# STM32F7.net
KiCad netlist of a schematic drawn in Altium Designer
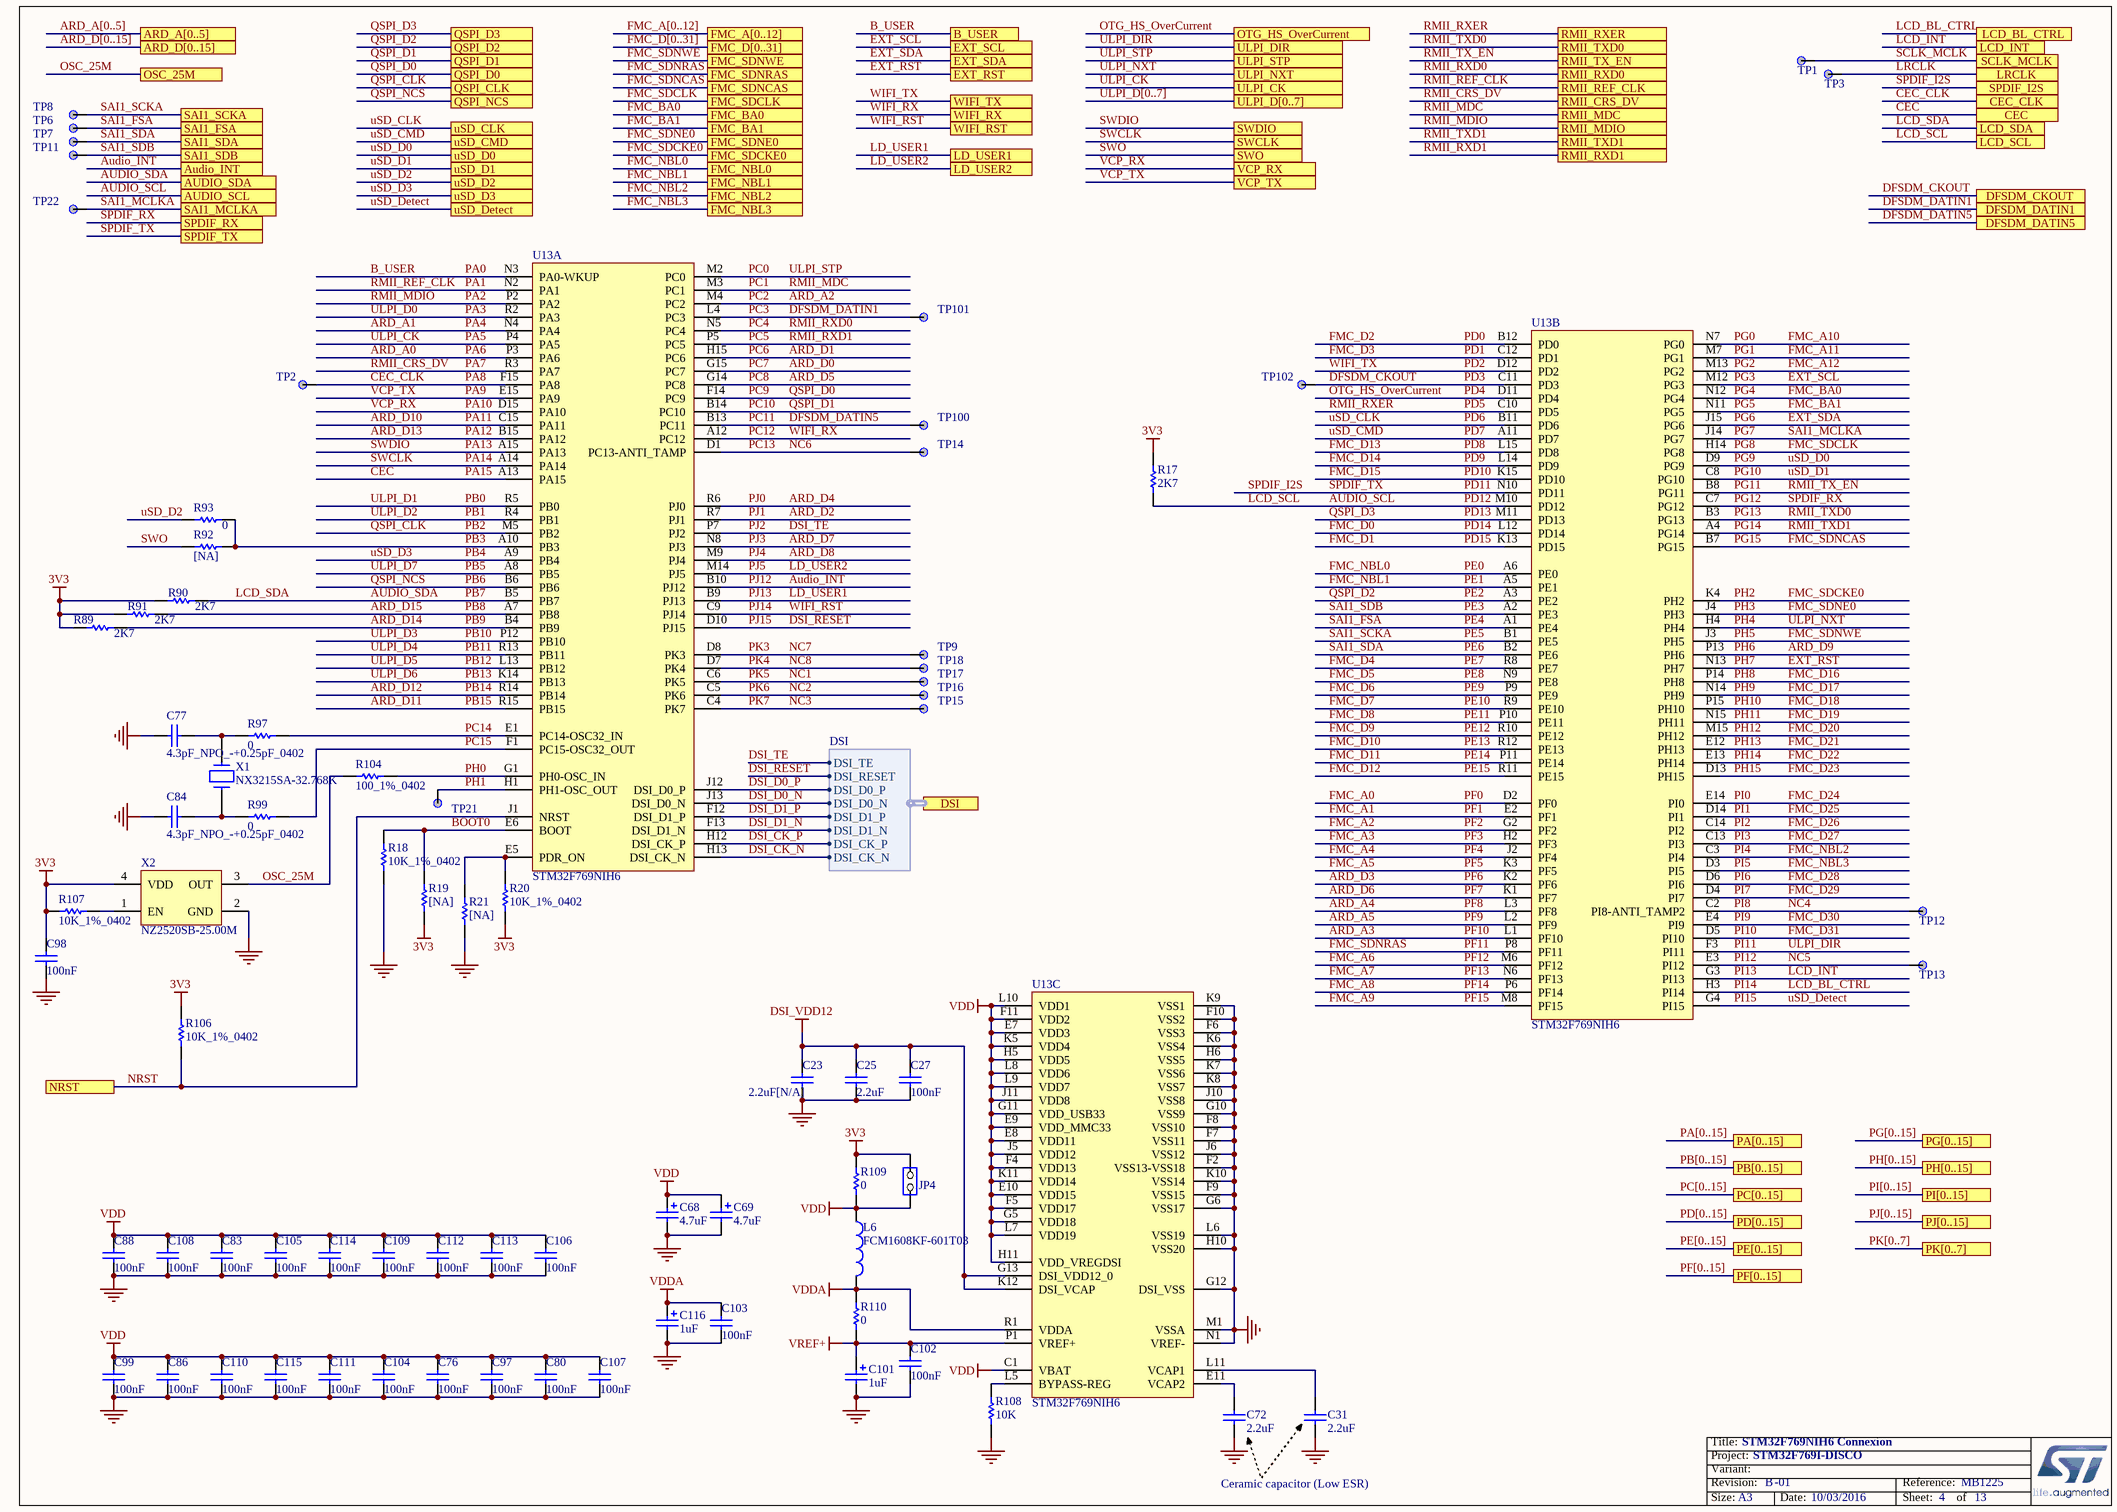
[diagram p0: STM32F7.SchDoc]

(export (version "E")
  (design (tool "Eeschema 10.0.6"))
  (components
    (comp (ref "C23")
      (value "2.2uF[N/A]")
      (footprint "1206C")
      (description "Capacitor,2.2uF,16V, X7R,10%,1206,YAGEO")
      (libsource (lib "MCD_TOOLS_CAPACITOR") (part "Cap_2.2uF_X7R_10%_1206"))
    )
    (comp (ref "C25")
      (value "2.2uF")
      (footprint "0603C")
      (description "Capacitor,2.2uF,10V, X5R,10%,0603,YAGEO")
      (libsource (lib "MCD_TOOLS_CAPACITOR") (part "Cap_2.2uF_X5R_10%_0603"))
    )
    (comp (ref "C27")
      (value "100nF")
      (footprint "0402C")
      (description "Capacitor,100nF,16V,X7R,10%,0402,YAGEO")
      (libsource (lib "MCD_TOOLS_CAPACITOR") (part "Cap_100nF_X7R_10%_0402"))
    )
    (comp (ref "C31")
      (value "2.2uF")
      (footprint "1206C")
      (description "Capacitor,2.2uF,16V, X7R,10%,1206,YAGEO")
      (libsource (lib "MCD_TOOLS") (part "Cap_2.2uF_X7R_10%_1206"))
    )
    (comp (ref "C68")
      (value "4.7uF")
      (footprint "TAN-A")
      (description "Polarized Capacitor,4.7uF,16V,10%,typeA,AVX")
      (libsource (lib "MCD_TOOLS") (part "Cap_4.7uF_POL_10%_TANA"))
    )
    (comp (ref "C69")
      (value "4.7uF")
      (footprint "TAN-A")
      (description "Polarized Capacitor,4.7uF,16V,10%,typeA,AVX")
      (libsource (lib "MCD_TOOLS") (part "Cap_4.7uF_POL_10%_TANA"))
    )
    (comp (ref "C72")
      (value "2.2uF")
      (footprint "1206C")
      (description "Capacitor,2.2uF,16V, X7R,10%,1206,YAGEO")
      (libsource (lib "MCD_TOOLS") (part "Cap_2.2uF_X7R_10%_1206"))
    )
    (comp (ref "C76")
      (value "100nF")
      (footprint "0402C")
      (description "Capacitor,100nF,16V,X7R,10%,0402,YAGEO")
      (libsource (lib "MCD_TOOLS") (part "Cap_100nF_X7R_10%_0402"))
    )
    (comp (ref "C77")
      (value "4.3pF_NPO_-+0.25pF_0402")
      (footprint "0402C")
      (description "Capacitor, 4.3pF, 16V, NPO, -+0.25pF, 0402, KEMET")
      (libsource (lib "MCD_TOOLS_CAPACITOR") (part "Cap_4.3pF_NPO_-+0.25pF_0402"))
    )
    (comp (ref "C80")
      (value "100nF")
      (footprint "0402C")
      (description "Capacitor,100nF,16V,X7R,10%,0402,YAGEO")
      (libsource (lib "MCD_TOOLS") (part "Cap_100nF_X7R_10%_0402"))
    )
    (comp (ref "C83")
      (value "100nF")
      (footprint "0402C")
      (description "Capacitor,100nF,16V,X7R,10%,0402,YAGEO")
      (libsource (lib "MCD_TOOLS") (part "Cap_100nF_X7R_10%_0402"))
    )
    (comp (ref "C84")
      (value "4.3pF_NPO_-+0.25pF_0402")
      (footprint "0402C")
      (description "Capacitor, 4.3pF, 16V, NPO, -+0.25pF, 0402, KEMET")
      (libsource (lib "MCD_TOOLS_CAPACITOR") (part "Cap_4.3pF_NPO_-+0.25pF_0402"))
    )
    (comp (ref "C86")
      (value "100nF")
      (footprint "0402C")
      (description "Capacitor,100nF,16V,X7R,10%,0402,YAGEO")
      (libsource (lib "MCD_TOOLS") (part "Cap_100nF_X7R_10%_0402"))
    )
    (comp (ref "C88")
      (value "100nF")
      (footprint "0402C")
      (description "Capacitor,100nF,16V,X7R,10%,0402,YAGEO")
      (libsource (lib "MCD_TOOLS") (part "Cap_100nF_X7R_10%_0402"))
    )
    (comp (ref "C97")
      (value "100nF")
      (footprint "0402C")
      (description "Capacitor,100nF,16V,X7R,10%,0402,YAGEO")
      (libsource (lib "MCD_TOOLS") (part "Cap_100nF_X7R_10%_0402"))
    )
    (comp (ref "C98")
      (value "100nF")
      (footprint "0402C")
      (description "Capacitor,100nF,16V,X7R,10%,0402,YAGEO")
      (libsource (lib "MCD_TOOLS") (part "Cap_100nF_X7R_10%_0402"))
    )
    (comp (ref "C99")
      (value "100nF")
      (footprint "0402C")
      (description "Capacitor,100nF,16V,X7R,10%,0402,YAGEO")
      (libsource (lib "MCD_TOOLS") (part "Cap_100nF_X7R_10%_0402"))
    )
    (comp (ref "C101")
      (value "1uF")
      (footprint "TAN-A")
      (description "Polarized Capacitor,1uF,16V,10%,typeA,AVX")
      (libsource (lib "MCD_TOOLS") (part "Cap_1uF_POL_10%_TANA"))
    )
    (comp (ref "C102")
      (value "100nF")
      (footprint "0402C")
      (description "Capacitor,100nF,16V,X7R,10%,0402,YAGEO")
      (libsource (lib "MCD_TOOLS") (part "Cap_100nF_X7R_10%_0402"))
    )
    (comp (ref "C103")
      (value "100nF")
      (footprint "0402C")
      (description "Capacitor,100nF,16V,X7R,10%,0402,YAGEO")
      (libsource (lib "MCD_TOOLS") (part "Cap_100nF_X7R_10%_0402"))
    )
    (comp (ref "C104")
      (value "100nF")
      (footprint "0402C")
      (description "Capacitor,100nF,16V,X7R,10%,0402,YAGEO")
      (libsource (lib "MCD_TOOLS") (part "Cap_100nF_X7R_10%_0402"))
    )
    (comp (ref "C105")
      (value "100nF")
      (footprint "0402C")
      (description "Capacitor,100nF,16V,X7R,10%,0402,YAGEO")
      (libsource (lib "MCD_TOOLS") (part "Cap_100nF_X7R_10%_0402"))
    )
    (comp (ref "C106")
      (value "100nF")
      (footprint "0402C")
      (description "Capacitor,100nF,16V,X7R,10%,0402,YAGEO")
      (libsource (lib "MCD_TOOLS") (part "Cap_100nF_X7R_10%_0402"))
    )
    (comp (ref "C107")
      (value "100nF")
      (footprint "0402C")
      (description "Capacitor,100nF,16V,X7R,10%,0402,YAGEO")
      (libsource (lib "MCD_TOOLS") (part "Cap_100nF_X7R_10%_0402"))
    )
    (comp (ref "C108")
      (value "100nF")
      (footprint "0402C")
      (description "Capacitor,100nF,16V,X7R,10%,0402,YAGEO")
      (libsource (lib "MCD_TOOLS") (part "Cap_100nF_X7R_10%_0402"))
    )
    (comp (ref "C109")
      (value "100nF")
      (footprint "0402C")
      (description "Capacitor,100nF,16V,X7R,10%,0402,YAGEO")
      (libsource (lib "MCD_TOOLS") (part "Cap_100nF_X7R_10%_0402"))
    )
    (comp (ref "C110")
      (value "100nF")
      (footprint "0402C")
      (description "Capacitor,100nF,16V,X7R,10%,0402,YAGEO")
      (libsource (lib "MCD_TOOLS") (part "Cap_100nF_X7R_10%_0402"))
    )
    (comp (ref "C111")
      (value "100nF")
      (footprint "0402C")
      (description "Capacitor,100nF,16V,X7R,10%,0402,YAGEO")
      (libsource (lib "MCD_TOOLS") (part "Cap_100nF_X7R_10%_0402"))
    )
    (comp (ref "C112")
      (value "100nF")
      (footprint "0402C")
      (description "Capacitor,100nF,16V,X7R,10%,0402,YAGEO")
      (libsource (lib "MCD_TOOLS") (part "Cap_100nF_X7R_10%_0402"))
    )
    (comp (ref "C113")
      (value "100nF")
      (footprint "0402C")
      (description "Capacitor,100nF,16V,X7R,10%,0402,YAGEO")
      (libsource (lib "MCD_TOOLS") (part "Cap_100nF_X7R_10%_0402"))
    )
    (comp (ref "C114")
      (value "100nF")
      (footprint "0402C")
      (description "Capacitor,100nF,16V,X7R,10%,0402,YAGEO")
      (libsource (lib "MCD_TOOLS") (part "Cap_100nF_X7R_10%_0402"))
    )
    (comp (ref "C115")
      (value "100nF")
      (footprint "0402C")
      (description "Capacitor,100nF,16V,X7R,10%,0402,YAGEO")
      (libsource (lib "MCD_TOOLS") (part "Cap_100nF_X7R_10%_0402"))
    )
    (comp (ref "C116")
      (value "1uF")
      (footprint "TAN-A")
      (description "Polarized Capacitor,1uF,16V,10%,typeA,AVX")
      (libsource (lib "MCD_TOOLS") (part "Cap_1uF_POL_10%_TANA"))
    )
    (comp (ref "JP4") (value "JP2") (footprint "SIP2") (libsource (lib "MCD_TOOLS_CONNECTOR") (part "JP2")))
    (comp (ref "L6")
      (value "FCM1608KF-601T03")
      (footprint "0603L")
      (description "Bead,600R,350mA,0603,FCM1608KF-601T03,Tai-tech")
      (libsource (lib "MCD_TOOLS") (part "BEAD_600R_350MA_0603"))
    )
    (comp (ref "R17")
      (value "2K7")
      (footprint "0402R")
      (description "Resistor,2K7,0402,1%,YAGEO")
      (libsource (lib "MCD_TOOLS") (part "Res_2K7_1%_0402"))
    )
    (comp (ref "R18")
      (value "10K_1%_0402")
      (footprint "0402R")
      (description "Resistor,10K,0402,1%,YAGEO")
      (libsource (lib "MCD_TOOLS") (part "Res_10K_1%_0402"))
    )
    (comp (ref "R19")
      (value "[NA]")
      (footprint "0402R")
      (description "Resistor,[NA],0402")
      (libsource (lib "MCD_TOOLS") (part "Res_NA_0402"))
    )
    (comp (ref "R20")
      (value "10K_1%_0402")
      (footprint "0402R")
      (description "Resistor,10K,0402,1%,YAGEO")
      (libsource (lib "MCD_TOOLS") (part "Res_10K_1%_0402"))
    )
    (comp (ref "R21")
      (value "[NA]")
      (footprint "0402R")
      (description "Resistor,[NA],0402")
      (libsource (lib "MCD_TOOLS") (part "Res_NA_0402"))
    )
    (comp (ref "R89")
      (value "2K7")
      (footprint "0402R")
      (description "Resistor,2K7,0402,1%,YAGEO")
      (libsource (lib "MCD_TOOLS") (part "Res_2K7_1%_0402"))
    )
    (comp (ref "R90")
      (value "2K7")
      (footprint "0402R")
      (description "Resistor,2K7,0402,1%,YAGEO")
      (libsource (lib "MCD_TOOLS") (part "Res_2K7_1%_0402"))
    )
    (comp (ref "R91")
      (value "2K7")
      (footprint "0402R")
      (description "Resistor,2K7,0402,1%,YAGEO")
      (libsource (lib "MCD_TOOLS") (part "Res_2K7_1%_0402"))
    )
    (comp (ref "R92")
      (value "[NA]")
      (footprint "0402R")
      (description "Resistor,[NA],0402")
      (libsource (lib "MCD_TOOLS_RESISTOR") (part "Res_NA_0402"))
    )
    (comp (ref "R93")
      (value "0")
      (footprint "0402R")
      (description "Resistor,0,0402,5%,YAGEO")
      (libsource (lib "MCD_TOOLS_RESISTOR") (part "Res_0_5%_0402"))
    )
    (comp (ref "R97")
      (value "0")
      (footprint "0402R")
      (description "Resistor,0,0402,5%,YAGEO")
      (libsource (lib "MCD_TOOLS") (part "Res_0_5%_0402"))
    )
    (comp (ref "R99")
      (value "0")
      (footprint "0402R")
      (description "Resistor,0,0402,5%,YAGEO")
      (libsource (lib "MCD_TOOLS") (part "Res_0_5%_0402"))
    )
    (comp (ref "R104")
      (value "100_1%_0402")
      (footprint "0402R")
      (description "Resistor,100,0402,1%,YAGEO")
      (libsource (lib "MCD_TOOLS") (part "Res_100_1%_0402"))
    )
    (comp (ref "R106")
      (value "10K_1%_0402")
      (footprint "0402R")
      (description "Resistor,10K,0402,1%,YAGEO")
      (libsource (lib "MCD_TOOLS") (part "Res_10K_1%_0402"))
    )
    (comp (ref "R107")
      (value "10K_1%_0402")
      (footprint "0402R")
      (description "Resistor,10K,0402,1%,YAGEO")
      (libsource (lib "MCD_TOOLS") (part "Res_10K_1%_0402"))
    )
    (comp (ref "R108")
      (value "10K")
      (footprint "0402R")
      (description "Resistor,10K,0402,1%,YAGEO")
      (libsource (lib "MCD_TOOLS") (part "Res_10K_1%_0402"))
    )
    (comp (ref "R109")
      (value "0")
      (footprint "0603R-GS")
      (description "Resistor,0,0603,5%,YAGEO")
      (libsource (lib "MCD_TOOLS") (part "Res_0_5%_0603"))
    )
    (comp (ref "R110")
      (value "0")
      (footprint "0603R-GS")
      (description "Resistor,0,0603,5%,YAGEO")
      (libsource (lib "MCD_TOOLS") (part "Res_0_5%_0603"))
    )
    (comp (ref "TP1")
      (value "TP")
      (footprint "TP_C40")
      (description "Test Point")
      (libsource (lib "MCD_TOOLS_CONNECTOR") (part "TP"))
    )
    (comp (ref "TP2")
      (value "TP")
      (footprint "TP_C40")
      (description "Test Point")
      (libsource (lib "MCD_TOOLS_CONNECTOR") (part "TP"))
    )
    (comp (ref "TP3")
      (value "TP")
      (footprint "TP_C40")
      (description "Test Point")
      (libsource (lib "MCD_TOOLS_CONNECTOR") (part "TP"))
    )
    (comp (ref "TP6")
      (value "TP")
      (footprint "TP_C40")
      (description "Test Point")
      (libsource (lib "MCD_TOOLS_CONNECTOR") (part "TP"))
    )
    (comp (ref "TP7")
      (value "TP")
      (footprint "TP_C40")
      (description "Test Point")
      (libsource (lib "MCD_TOOLS_CONNECTOR") (part "TP"))
    )
    (comp (ref "TP8")
      (value "TP")
      (footprint "TP_C40")
      (description "Test Point")
      (libsource (lib "MCD_TOOLS_CONNECTOR") (part "TP"))
    )
    (comp (ref "TP9")
      (value "TP")
      (footprint "TP_C40")
      (description "Test Point")
      (libsource (lib "MCD_TOOLS_CONNECTOR") (part "TP"))
    )
    (comp (ref "TP11")
      (value "TP")
      (footprint "TP_C40")
      (description "Test Point")
      (libsource (lib "MCD_TOOLS_CONNECTOR") (part "TP"))
    )
    (comp (ref "TP12")
      (value "TP")
      (footprint "TP_C40")
      (description "Test Point")
      (libsource (lib "MCD_TOOLS_CONNECTOR") (part "TP"))
    )
    (comp (ref "TP13")
      (value "TP")
      (footprint "TP_C40")
      (description "Test Point")
      (libsource (lib "MCD_TOOLS_CONNECTOR") (part "TP"))
    )
    (comp (ref "TP14")
      (value "TP")
      (footprint "TP_C40")
      (description "Test Point")
      (libsource (lib "MCD_TOOLS_CONNECTOR") (part "TP"))
    )
    (comp (ref "TP15")
      (value "TP")
      (footprint "TP_C40")
      (description "Test Point")
      (libsource (lib "MCD_TOOLS_CONNECTOR") (part "TP"))
    )
    (comp (ref "TP16")
      (value "TP")
      (footprint "TP_C40")
      (description "Test Point")
      (libsource (lib "MCD_TOOLS_CONNECTOR") (part "TP"))
    )
    (comp (ref "TP17")
      (value "TP")
      (footprint "TP_C40")
      (description "Test Point")
      (libsource (lib "MCD_TOOLS_CONNECTOR") (part "TP"))
    )
    (comp (ref "TP18")
      (value "TP")
      (footprint "TP_C40")
      (description "Test Point")
      (libsource (lib "MCD_TOOLS_CONNECTOR") (part "TP"))
    )
    (comp (ref "TP21")
      (value "TP")
      (footprint "TP_C40")
      (description "Test Point")
      (libsource (lib "MCD_TOOLS_CONNECTOR") (part "TP"))
    )
    (comp (ref "TP22")
      (value "TP")
      (footprint "TP_C40")
      (description "Test Point")
      (libsource (lib "MCD_TOOLS_CONNECTOR") (part "TP"))
    )
    (comp (ref "TP100")
      (value "TP")
      (footprint "TP_C40")
      (description "Test Point")
      (libsource (lib "MCD_TOOLS_CONNECTOR") (part "TP"))
    )
    (comp (ref "TP101")
      (value "TP")
      (footprint "TP_C40")
      (description "Test Point")
      (libsource (lib "MCD_TOOLS_CONNECTOR") (part "TP"))
    )
    (comp (ref "TP102")
      (value "TP")
      (footprint "TP_C40")
      (description "Test Point")
      (libsource (lib "MCD_TOOLS_CONNECTOR") (part "TP"))
    )
    (comp (ref "U13")
      (value "STM32F769NIH6")
      (footprint "BGA216_0R8_13X13")
      (description "STM32F769NIH6 (STM32F7 Big Birdie) TBGA216")
      (libsource (lib "MCD_TOOLS_MCU") (part "STM32F769NIH6U"))
    )
    (comp (ref "X1")
      (value "NX3215SA-32.768K")
      (footprint "XTAL_2SM_3R2X1R5")
      (description "Crystal 32.768kHz, 6pF, -+20PPM, R=50K, SMD")
      (libsource (lib "MCD_TOOLS") (part "XTAL_32K_NX3215SA"))
    )
    (comp (ref "X2")
      (value "NZ2520SB-25.00M")
      (footprint "OSC_4SM_2R5X2")
      (description "Oscillator 25.00Mhz, -+50PPM, 3.3V, Temp -55 to +125°C")
      (libsource (lib "MCD_TOOLS_MISCELLANEOUS") (part "OSC_25M_NZ2520SB"))
    )
  )
  (nets
    (net (code "11") (name "/ARD_A0") (class "Default")
      (node (ref "U13") (pin "P3") (pinfunction "PA6_P3") (pintype "passive"))
    )
    (net (code "12") (name "/ARD_A1") (class "Default")
      (node (ref "U13") (pin "N4") (pinfunction "PA4_N4") (pintype "passive"))
    )
    (net (code "13") (name "/ARD_A2") (class "Default")
      (node (ref "U13") (pin "M4") (pinfunction "PC2_M4") (pintype "passive"))
    )
    (net (code "14") (name "/ARD_A3") (class "Default")
      (node (ref "U13") (pin "L1") (pinfunction "PF10_L1") (pintype "passive"))
    )
    (net (code "15") (name "/ARD_A4") (class "Default")
      (node (ref "U13") (pin "L3") (pinfunction "PF8_L3") (pintype "passive"))
    )
    (net (code "16") (name "/ARD_A5") (class "Default")
      (node (ref "U13") (pin "L2") (pinfunction "PF9_L2") (pintype "passive"))
    )
    (net (code "18") (name "/ARD_D0") (class "Default")
      (node (ref "U13") (pin "G15") (pinfunction "PC7_G15") (pintype "passive"))
    )
    (net (code "19") (name "/ARD_D1") (class "Default")
      (node (ref "U13") (pin "H15") (pinfunction "PC6_H15") (pintype "passive"))
    )
    (net (code "20") (name "/ARD_D2") (class "Default")
      (node (ref "U13") (pin "R7") (pinfunction "PJ1_R7") (pintype "passive"))
    )
    (net (code "21") (name "/ARD_D3") (class "Default")
      (node (ref "U13") (pin "K2") (pinfunction "PF6_K2") (pintype "passive"))
    )
    (net (code "22") (name "/ARD_D4") (class "Default")
      (node (ref "U13") (pin "R6") (pinfunction "PJ0_R6") (pintype "passive"))
    )
    (net (code "23") (name "/ARD_D5") (class "Default")
      (node (ref "U13") (pin "G14") (pinfunction "PC8_G14") (pintype "passive"))
    )
    (net (code "24") (name "/ARD_D6") (class "Default")
      (node (ref "U13") (pin "K1") (pinfunction "PF7_K1") (pintype "passive"))
    )
    (net (code "25") (name "/ARD_D7") (class "Default")
      (node (ref "U13") (pin "N8") (pinfunction "PJ3_N8") (pintype "passive"))
    )
    (net (code "26") (name "/ARD_D8") (class "Default")
      (node (ref "U13") (pin "M9") (pinfunction "PJ4_M9") (pintype "passive"))
    )
    (net (code "27") (name "/ARD_D9") (class "Default")
      (node (ref "U13") (pin "P13") (pinfunction "PH6_P13") (pintype "passive"))
    )
    (net (code "28") (name "/ARD_D10") (class "Default")
      (node (ref "U13") (pin "C15") (pinfunction "PA11_C15") (pintype "passive"))
    )
    (net (code "29") (name "/ARD_D11") (class "Default")
      (node (ref "U13") (pin "R15") (pinfunction "PB15_R15") (pintype "passive"))
    )
    (net (code "30") (name "/ARD_D12") (class "Default")
      (node (ref "U13") (pin "R14") (pinfunction "PB14_R14") (pintype "passive"))
    )
    (net (code "31") (name "/ARD_D13") (class "Default")
      (node (ref "U13") (pin "B15") (pinfunction "PA12_B15") (pintype "passive"))
    )
    (net (code "32") (name "/ARD_D14") (class "Default")
      (node (ref "R89") (pin "2") (pinfunction "2_2") (pintype "passive"))
      (node (ref "U13") (pin "B4") (pinfunction "PB9_B4") (pintype "passive"))
    )
    (net (code "33") (name "/ARD_D15") (class "Default")
      (node (ref "R91") (pin "2") (pinfunction "2_2") (pintype "passive"))
      (node (ref "U13") (pin "A7") (pinfunction "PB8_A7") (pintype "passive"))
    )
    (net (code "35") (name "/BOOT0") (class "Default")
      (node (ref "R18") (pin "2") (pinfunction "2_2") (pintype "passive"))
      (node (ref "R19") (pin "2") (pinfunction "2_2") (pintype "passive"))
      (node (ref "U13") (pin "E6") (pinfunction "BOOT_E6") (pintype "passive"))
    )
    (net (code "36") (name "/DSI_CK_N") (class "Default")
      (node (ref "U13") (pin "H13") (pinfunction "DSI_CK_N_H13") (pintype "passive"))
    )
    (net (code "37") (name "/DSI_CK_P") (class "Default")
      (node (ref "U13") (pin "H12") (pinfunction "DSI_CK_P_H12") (pintype "passive"))
    )
    (net (code "38") (name "/DSI_D0_N") (class "Default")
      (node (ref "U13") (pin "J13") (pinfunction "DSI_D0_N_J13") (pintype "passive"))
    )
    (net (code "39") (name "/DSI_D0_P") (class "Default")
      (node (ref "U13") (pin "J12") (pinfunction "DSI_D0_P_J12") (pintype "passive"))
    )
    (net (code "40") (name "/DSI_D1_N") (class "Default")
      (node (ref "U13") (pin "F13") (pinfunction "DSI_D1_N_F13") (pintype "passive"))
    )
    (net (code "41") (name "/DSI_D1_P") (class "Default")
      (node (ref "U13") (pin "F12") (pinfunction "DSI_D1_P_F12") (pintype "passive"))
    )
    (net (code "42") (name "/FMC_A0") (class "Default")
      (node (ref "U13") (pin "D2") (pinfunction "PF0_D2") (pintype "passive"))
    )
    (net (code "43") (name "/FMC_A1") (class "Default")
      (node (ref "U13") (pin "E2") (pinfunction "PF1_E2") (pintype "passive"))
    )
    (net (code "44") (name "/FMC_A2") (class "Default")
      (node (ref "U13") (pin "G2") (pinfunction "PF2_G2") (pintype "passive"))
    )
    (net (code "45") (name "/FMC_A3") (class "Default")
      (node (ref "U13") (pin "H2") (pinfunction "PF3_H2") (pintype "passive"))
    )
    (net (code "46") (name "/FMC_A4") (class "Default")
      (node (ref "U13") (pin "J2") (pinfunction "PF4_J2") (pintype "passive"))
    )
    (net (code "47") (name "/FMC_A5") (class "Default")
      (node (ref "U13") (pin "K3") (pinfunction "PF5_K3") (pintype "passive"))
    )
    (net (code "48") (name "/FMC_A6") (class "Default")
      (node (ref "U13") (pin "M6") (pinfunction "PF12_M6") (pintype "passive"))
    )
    (net (code "49") (name "/FMC_A7") (class "Default")
      (node (ref "U13") (pin "N6") (pinfunction "PF13_N6") (pintype "passive"))
    )
    (net (code "50") (name "/FMC_A8") (class "Default")
      (node (ref "U13") (pin "P6") (pinfunction "PF14_P6") (pintype "passive"))
    )
    (net (code "51") (name "/FMC_A9") (class "Default")
      (node (ref "U13") (pin "M8") (pinfunction "PF15_M8") (pintype "passive"))
    )
    (net (code "52") (name "/FMC_A10") (class "Default")
      (node (ref "U13") (pin "N7") (pinfunction "PG0_N7") (pintype "passive"))
    )
    (net (code "53") (name "/FMC_A11") (class "Default")
      (node (ref "U13") (pin "M7") (pinfunction "PG1_M7") (pintype "passive"))
    )
    (net (code "54") (name "/FMC_A12") (class "Default")
      (node (ref "U13") (pin "M13") (pinfunction "PG2_M13") (pintype "passive"))
    )
    (net (code "56") (name "/FMC_D0") (class "Default")
      (node (ref "U13") (pin "L12") (pinfunction "PD14_L12") (pintype "passive"))
    )
    (net (code "57") (name "/FMC_D1") (class "Default")
      (node (ref "U13") (pin "K13") (pinfunction "PD15_K13") (pintype "passive"))
    )
    (net (code "58") (name "/FMC_D2") (class "Default")
      (node (ref "U13") (pin "B12") (pinfunction "PD0_B12") (pintype "passive"))
    )
    (net (code "59") (name "/FMC_D3") (class "Default")
      (node (ref "U13") (pin "C12") (pinfunction "PD1_C12") (pintype "passive"))
    )
    (net (code "60") (name "/FMC_D4") (class "Default")
      (node (ref "U13") (pin "R8") (pinfunction "PE7_R8") (pintype "passive"))
    )
    (net (code "61") (name "/FMC_D5") (class "Default")
      (node (ref "U13") (pin "N9") (pinfunction "PE8_N9") (pintype "passive"))
    )
    (net (code "62") (name "/FMC_D6") (class "Default")
      (node (ref "U13") (pin "P9") (pinfunction "PE9_P9") (pintype "passive"))
    )
    (net (code "63") (name "/FMC_D7") (class "Default")
      (node (ref "U13") (pin "R9") (pinfunction "PE10_R9") (pintype "passive"))
    )
    (net (code "64") (name "/FMC_D8") (class "Default")
      (node (ref "U13") (pin "P10") (pinfunction "PE11_P10") (pintype "passive"))
    )
    (net (code "65") (name "/FMC_D9") (class "Default")
      (node (ref "U13") (pin "R10") (pinfunction "PE12_R10") (pintype "passive"))
    )
    (net (code "66") (name "/FMC_D10") (class "Default")
      (node (ref "U13") (pin "R12") (pinfunction "PE13_R12") (pintype "passive"))
    )
    (net (code "67") (name "/FMC_D11") (class "Default")
      (node (ref "U13") (pin "P11") (pinfunction "PE14_P11") (pintype "passive"))
    )
    (net (code "68") (name "/FMC_D12") (class "Default")
      (node (ref "U13") (pin "R11") (pinfunction "PE15_R11") (pintype "passive"))
    )
    (net (code "69") (name "/FMC_D13") (class "Default")
      (node (ref "U13") (pin "L15") (pinfunction "PD8_L15") (pintype "passive"))
    )
    (net (code "70") (name "/FMC_D14") (class "Default")
      (node (ref "U13") (pin "L14") (pinfunction "PD9_L14") (pintype "passive"))
    )
    (net (code "71") (name "/FMC_D15") (class "Default")
      (node (ref "U13") (pin "K15") (pinfunction "PD10_K15") (pintype "passive"))
    )
    (net (code "72") (name "/FMC_D16") (class "Default")
      (node (ref "U13") (pin "P14") (pinfunction "PH8_P14") (pintype "passive"))
    )
    (net (code "73") (name "/FMC_D17") (class "Default")
      (node (ref "U13") (pin "N14") (pinfunction "PH9_N14") (pintype "passive"))
    )
    (net (code "74") (name "/FMC_D18") (class "Default")
      (node (ref "U13") (pin "P15") (pinfunction "PH10_P15") (pintype "passive"))
    )
    (net (code "75") (name "/FMC_D19") (class "Default")
      (node (ref "U13") (pin "N15") (pinfunction "PH11_N15") (pintype "passive"))
    )
    (net (code "76") (name "/FMC_D20") (class "Default")
      (node (ref "U13") (pin "M15") (pinfunction "PH12_M15") (pintype "passive"))
    )
    (net (code "77") (name "/FMC_D21") (class "Default")
      (node (ref "U13") (pin "E12") (pinfunction "PH13_E12") (pintype "passive"))
    )
    (net (code "78") (name "/FMC_D22") (class "Default")
      (node (ref "U13") (pin "E13") (pinfunction "PH14_E13") (pintype "passive"))
    )
    (net (code "79") (name "/FMC_D23") (class "Default")
      (node (ref "U13") (pin "D13") (pinfunction "PH15_D13") (pintype "passive"))
    )
    (net (code "80") (name "/FMC_D24") (class "Default")
      (node (ref "U13") (pin "E14") (pinfunction "PI0_E14") (pintype "passive"))
    )
    (net (code "81") (name "/FMC_D25") (class "Default")
      (node (ref "U13") (pin "D14") (pinfunction "PI1_D14") (pintype "passive"))
    )
    (net (code "82") (name "/FMC_D26") (class "Default")
      (node (ref "U13") (pin "C14") (pinfunction "PI2_C14") (pintype "passive"))
    )
    (net (code "83") (name "/FMC_D27") (class "Default")
      (node (ref "U13") (pin "C13") (pinfunction "PI3_C13") (pintype "passive"))
    )
    (net (code "84") (name "/FMC_D28") (class "Default")
      (node (ref "U13") (pin "D6") (pinfunction "PI6_D6") (pintype "passive"))
    )
    (net (code "85") (name "/FMC_D29") (class "Default")
      (node (ref "U13") (pin "D4") (pinfunction "PI7_D4") (pintype "passive"))
    )
    (net (code "86") (name "/FMC_D30") (class "Default")
      (node (ref "U13") (pin "E4") (pinfunction "PI9_E4") (pintype "passive"))
    )
    (net (code "87") (name "/FMC_D31") (class "Default")
      (node (ref "U13") (pin "D5") (pinfunction "PI10_D5") (pintype "passive"))
    )
    (net (code "89") (name "/LRCLK") (class "Default")
      (node (ref "TP3") (pin "1") (pinfunction "1_1") (pintype "passive"))
    )
    (net (code "90") (name "/NRST") (class "Default")
      (node (ref "R106") (pin "1") (pinfunction "1_1") (pintype "passive"))
      (node (ref "U13") (pin "J1") (pinfunction "NRST_J1") (pintype "passive"))
    )
    (net (code "91") (name "/OSC_25M") (class "Default")
      (node (ref "R104") (pin "1") (pinfunction "1_1") (pintype "passive"))
      (node (ref "X2") (pin "3") (pinfunction "OUT_3") (pintype "passive"))
    )
    (net (code "92") (name "/PA0") (class "Default")
      (node (ref "U13") (pin "N3") (pinfunction "PA0-WKUP_N3") (pintype "passive"))
    )
    (net (code "93") (name "/PA1") (class "Default")
      (node (ref "U13") (pin "N2") (pinfunction "PA1_N2") (pintype "passive"))
    )
    (net (code "94") (name "/PA2") (class "Default")
      (node (ref "U13") (pin "P2") (pinfunction "PA2_P2") (pintype "passive"))
    )
    (net (code "95") (name "/PA5") (class "Default")
      (node (ref "U13") (pin "P4") (pinfunction "PA5_P4") (pintype "passive"))
    )
    (net (code "96") (name "/PA7") (class "Default")
      (node (ref "U13") (pin "R3") (pinfunction "PA7_R3") (pintype "passive"))
    )
    (net (code "97") (name "/PA8") (class "Default")
      (node (ref "TP2") (pin "1") (pinfunction "1_1") (pintype "passive"))
      (node (ref "U13") (pin "F15") (pinfunction "PA8_F15") (pintype "passive"))
    )
    (net (code "98") (name "/PA9") (class "Default")
      (node (ref "U13") (pin "E15") (pinfunction "PA9_E15") (pintype "passive"))
    )
    (net (code "99") (name "/PA10") (class "Default")
      (node (ref "U13") (pin "D15") (pinfunction "PA10_D15") (pintype "passive"))
    )
    (net (code "100") (name "/PA13") (class "Default")
      (node (ref "U13") (pin "A15") (pinfunction "PA13_A15") (pintype "passive"))
    )
    (net (code "101") (name "/PA14") (class "Default")
      (node (ref "U13") (pin "A14") (pinfunction "PA14_A14") (pintype "passive"))
    )
    (net (code "102") (name "/PA15") (class "Default")
      (node (ref "U13") (pin "A13") (pinfunction "PA15_A13") (pintype "passive"))
    )
    (net (code "104") (name "/PB2") (class "Default")
      (node (ref "U13") (pin "M5") (pinfunction "PB2_M5") (pintype "passive"))
    )
    (net (code "105") (name "/PB3") (class "Default")
      (node (ref "R92") (pin "2") (pinfunction "2_2") (pintype "passive"))
      (node (ref "R93") (pin "2") (pinfunction "2_2") (pintype "passive"))
      (node (ref "U13") (pin "A10") (pinfunction "PB3_A10") (pintype "passive"))
    )
    (net (code "106") (name "/PB4") (class "Default")
      (node (ref "U13") (pin "A9") (pinfunction "PB4_A9") (pintype "passive"))
    )
    (net (code "107") (name "/PB6") (class "Default")
      (node (ref "U13") (pin "B6") (pinfunction "PB6_B6") (pintype "passive"))
    )
    (net (code "108") (name "/PB7") (class "Default")
      (node (ref "R90") (pin "2") (pinfunction "2_2") (pintype "passive"))
      (node (ref "U13") (pin "B5") (pinfunction "PB7_B5") (pintype "passive"))
    )
    (net (code "110") (name "/PC0") (class "Default")
      (node (ref "U13") (pin "M2") (pinfunction "PC0_M2") (pintype "passive"))
    )
    (net (code "111") (name "/PC1") (class "Default")
      (node (ref "U13") (pin "M3") (pinfunction "PC1_M3") (pintype "passive"))
    )
    (net (code "112") (name "/PC3") (class "Default")
      (node (ref "TP101") (pin "1") (pinfunction "1_1") (pintype "passive"))
      (node (ref "U13") (pin "L4") (pinfunction "PC3_L4") (pintype "passive"))
    )
    (net (code "113") (name "/PC4") (class "Default")
      (node (ref "U13") (pin "N5") (pinfunction "PC4_N5") (pintype "passive"))
    )
    (net (code "114") (name "/PC5") (class "Default")
      (node (ref "U13") (pin "P5") (pinfunction "PC5_P5") (pintype "passive"))
    )
    (net (code "115") (name "/PC9") (class "Default")
      (node (ref "U13") (pin "F14") (pinfunction "PC9_F14") (pintype "passive"))
    )
    (net (code "116") (name "/PC10") (class "Default")
      (node (ref "U13") (pin "B14") (pinfunction "PC10_B14") (pintype "passive"))
    )
    (net (code "117") (name "/PC11") (class "Default")
      (node (ref "TP100") (pin "1") (pinfunction "1_1") (pintype "passive"))
      (node (ref "U13") (pin "B13") (pinfunction "PC11_B13") (pintype "passive"))
    )
    (net (code "118") (name "/PC12") (class "Default")
      (node (ref "U13") (pin "A12") (pinfunction "PC12_A12") (pintype "passive"))
    )
    (net (code "119") (name "/PC13") (class "Default")
      (node (ref "TP14") (pin "1") (pinfunction "1_1") (pintype "passive"))
      (node (ref "U13") (pin "D1") (pinfunction "PC13-ANTI_TAMP_D1") (pintype "passive"))
    )
    (net (code "120") (name "/PC14") (class "Default")
      (node (ref "R97") (pin "2") (pinfunction "2_2") (pintype "passive"))
      (node (ref "U13") (pin "E1") (pinfunction "PC14-OSC32_IN_E1") (pintype "passive"))
    )
    (net (code "121") (name "/PC15") (class "Default")
      (node (ref "R99") (pin "2") (pinfunction "2_2") (pintype "passive"))
      (node (ref "U13") (pin "F1") (pinfunction "PC15-OSC32_OUT_F1") (pintype "passive"))
    )
    (net (code "123") (name "/PD2") (class "Default")
      (node (ref "U13") (pin "D12") (pinfunction "PD2_D12") (pintype "passive"))
    )
    (net (code "124") (name "/PD3") (class "Default")
      (node (ref "TP102") (pin "1") (pinfunction "1_1") (pintype "passive"))
      (node (ref "U13") (pin "C11") (pinfunction "PD3_C11") (pintype "passive"))
    )
    (net (code "125") (name "/PD4") (class "Default")
      (node (ref "U13") (pin "D11") (pinfunction "PD4_D11") (pintype "passive"))
    )
    (net (code "126") (name "/PD5") (class "Default")
      (node (ref "U13") (pin "C10") (pinfunction "PD5_C10") (pintype "passive"))
    )
    (net (code "127") (name "/PD6") (class "Default")
      (node (ref "U13") (pin "B11") (pinfunction "PD6_B11") (pintype "passive"))
    )
    (net (code "128") (name "/PD7") (class "Default")
      (node (ref "U13") (pin "A11") (pinfunction "PD7_A11") (pintype "passive"))
    )
    (net (code "129") (name "/PD11") (class "Default")
      (node (ref "U13") (pin "N10") (pinfunction "PD11_N10") (pintype "passive"))
    )
    (net (code "130") (name "/PD12") (class "Default")
      (node (ref "R17") (pin "1") (pinfunction "1_1") (pintype "passive"))
      (node (ref "U13") (pin "M10") (pinfunction "PD12_M10") (pintype "passive"))
    )
    (net (code "131") (name "/PD13") (class "Default")
      (node (ref "U13") (pin "M11") (pinfunction "PD13_M11") (pintype "passive"))
    )
    (net (code "133") (name "/PE0") (class "Default")
      (node (ref "U13") (pin "A6") (pinfunction "PE0_A6") (pintype "passive"))
    )
    (net (code "134") (name "/PE1") (class "Default")
      (node (ref "U13") (pin "A5") (pinfunction "PE1_A5") (pintype "passive"))
    )
    (net (code "135") (name "/PE2") (class "Default")
      (node (ref "U13") (pin "A3") (pinfunction "PE2_A3") (pintype "passive"))
    )
    (net (code "136") (name "/PE3") (class "Default")
      (node (ref "TP11") (pin "1") (pinfunction "1_1") (pintype "passive"))
      (node (ref "U13") (pin "A2") (pinfunction "PE3_A2") (pintype "passive"))
    )
    (net (code "137") (name "/PE4") (class "Default")
      (node (ref "TP6") (pin "1") (pinfunction "1_1") (pintype "passive"))
      (node (ref "U13") (pin "A1") (pinfunction "PE4_A1") (pintype "passive"))
    )
    (net (code "138") (name "/PE5") (class "Default")
      (node (ref "TP8") (pin "1") (pinfunction "1_1") (pintype "passive"))
      (node (ref "U13") (pin "B1") (pinfunction "PE5_B1") (pintype "passive"))
    )
    (net (code "139") (name "/PE6") (class "Default")
      (node (ref "TP7") (pin "1") (pinfunction "1_1") (pintype "passive"))
      (node (ref "U13") (pin "B2") (pinfunction "PE6_B2") (pintype "passive"))
    )
    (net (code "141") (name "/PF11") (class "Default")
      (node (ref "U13") (pin "P8") (pinfunction "PF11_P8") (pintype "passive"))
    )
    (net (code "143") (name "/PG3") (class "Default")
      (node (ref "U13") (pin "M12") (pinfunction "PG3_M12") (pintype "passive"))
    )
    (net (code "144") (name "/PG4") (class "Default")
      (node (ref "U13") (pin "N12") (pinfunction "PG4_N12") (pintype "passive"))
    )
    (net (code "145") (name "/PG5") (class "Default")
      (node (ref "U13") (pin "N11") (pinfunction "PG5_N11") (pintype "passive"))
    )
    (net (code "146") (name "/PG6") (class "Default")
      (node (ref "U13") (pin "J15") (pinfunction "PG6_J15") (pintype "passive"))
    )
    (net (code "147") (name "/PG7") (class "Default")
      (node (ref "TP22") (pin "1") (pinfunction "1_1") (pintype "passive"))
      (node (ref "U13") (pin "J14") (pinfunction "PG7_J14") (pintype "passive"))
    )
    (net (code "148") (name "/PG8") (class "Default")
      (node (ref "U13") (pin "H14") (pinfunction "PG8_H14") (pintype "passive"))
    )
    (net (code "149") (name "/PG9") (class "Default")
      (node (ref "U13") (pin "D9") (pinfunction "PG9_D9") (pintype "passive"))
    )
    (net (code "150") (name "/PG10") (class "Default")
      (node (ref "U13") (pin "C8") (pinfunction "PG10_C8") (pintype "passive"))
    )
    (net (code "151") (name "/PG11") (class "Default")
      (node (ref "U13") (pin "B8") (pinfunction "PG11_B8") (pintype "passive"))
    )
    (net (code "152") (name "/PG12") (class "Default")
      (node (ref "U13") (pin "C7") (pinfunction "PG12_C7") (pintype "passive"))
    )
    (net (code "153") (name "/PG13") (class "Default")
      (node (ref "U13") (pin "B3") (pinfunction "PG13_B3") (pintype "passive"))
    )
    (net (code "154") (name "/PG14") (class "Default")
      (node (ref "U13") (pin "A4") (pinfunction "PG14_A4") (pintype "passive"))
    )
    (net (code "155") (name "/PG15") (class "Default")
      (node (ref "U13") (pin "B7") (pinfunction "PG15_B7") (pintype "passive"))
    )
    (net (code "157") (name "/PH0") (class "Default")
      (node (ref "R104") (pin "2") (pinfunction "2_2") (pintype "passive"))
      (node (ref "U13") (pin "G1") (pinfunction "PH0-OSC_IN_G1") (pintype "passive"))
    )
    (net (code "158") (name "/PH1") (class "Default")
      (node (ref "TP21") (pin "1") (pinfunction "1_1") (pintype "passive"))
      (node (ref "U13") (pin "H1") (pinfunction "PH1-OSC_OUT_H1") (pintype "passive"))
    )
    (net (code "159") (name "/PH2") (class "Default")
      (node (ref "U13") (pin "K4") (pinfunction "PH2_K4") (pintype "passive"))
    )
    (net (code "160") (name "/PH3") (class "Default")
      (node (ref "U13") (pin "J4") (pinfunction "PH3_J4") (pintype "passive"))
    )
    (net (code "161") (name "/PH4") (class "Default")
      (node (ref "U13") (pin "H4") (pinfunction "PH4_H4") (pintype "passive"))
    )
    (net (code "162") (name "/PH5") (class "Default")
      (node (ref "U13") (pin "J3") (pinfunction "PH5_J3") (pintype "passive"))
    )
    (net (code "163") (name "/PH7") (class "Default")
      (node (ref "U13") (pin "N13") (pinfunction "PH7_N13") (pintype "passive"))
    )
    (net (code "165") (name "/PI4") (class "Default")
      (node (ref "U13") (pin "C3") (pinfunction "PI4_C3") (pintype "passive"))
    )
    (net (code "166") (name "/PI5") (class "Default")
      (node (ref "U13") (pin "D3") (pinfunction "PI5_D3") (pintype "passive"))
    )
    (net (code "167") (name "/PI8") (class "Default")
      (node (ref "TP12") (pin "1") (pinfunction "1_1") (pintype "passive"))
      (node (ref "U13") (pin "C2") (pinfunction "PI8-ANTI_TAMP2_C2") (pintype "passive"))
    )
    (net (code "168") (name "/PI11") (class "Default")
      (node (ref "U13") (pin "F3") (pinfunction "PI11_F3") (pintype "passive"))
    )
    (net (code "169") (name "/PI12") (class "Default")
      (node (ref "TP13") (pin "1") (pinfunction "1_1") (pintype "passive"))
      (node (ref "U13") (pin "E3") (pinfunction "PI12_E3") (pintype "passive"))
    )
    (net (code "170") (name "/PI13") (class "Default")
      (node (ref "U13") (pin "G3") (pinfunction "PI13_G3") (pintype "passive"))
    )
    (net (code "171") (name "/PI14") (class "Default")
      (node (ref "U13") (pin "H3") (pinfunction "PI14_H3") (pintype "passive"))
    )
    (net (code "172") (name "/PI15") (class "Default")
      (node (ref "U13") (pin "G4") (pinfunction "PI15_G4") (pintype "passive"))
    )
    (net (code "174") (name "/PJ2") (class "Default")
      (node (ref "U13") (pin "P7") (pinfunction "PJ2_P7") (pintype "passive"))
    )
    (net (code "175") (name "/PJ5") (class "Default")
      (node (ref "U13") (pin "M14") (pinfunction "PJ5_M14") (pintype "passive"))
    )
    (net (code "176") (name "/PJ12") (class "Default")
      (node (ref "U13") (pin "B10") (pinfunction "PJ12_B10") (pintype "passive"))
    )
    (net (code "177") (name "/PJ13") (class "Default")
      (node (ref "U13") (pin "B9") (pinfunction "PJ13_B9") (pintype "passive"))
    )
    (net (code "178") (name "/PJ14") (class "Default")
      (node (ref "U13") (pin "C9") (pinfunction "PJ14_C9") (pintype "passive"))
    )
    (net (code "179") (name "/PJ15") (class "Default")
      (node (ref "U13") (pin "D10") (pinfunction "PJ15_D10") (pintype "passive"))
    )
    (net (code "181") (name "/PK3") (class "Default")
      (node (ref "TP9") (pin "1") (pinfunction "1_1") (pintype "passive"))
      (node (ref "U13") (pin "D8") (pinfunction "PK3_D8") (pintype "passive"))
    )
    (net (code "182") (name "/PK4") (class "Default")
      (node (ref "TP18") (pin "1") (pinfunction "1_1") (pintype "passive"))
      (node (ref "U13") (pin "D7") (pinfunction "PK4_D7") (pintype "passive"))
    )
    (net (code "183") (name "/PK5") (class "Default")
      (node (ref "TP17") (pin "1") (pinfunction "1_1") (pintype "passive"))
      (node (ref "U13") (pin "C6") (pinfunction "PK5_C6") (pintype "passive"))
    )
    (net (code "184") (name "/PK6") (class "Default")
      (node (ref "TP16") (pin "1") (pinfunction "1_1") (pintype "passive"))
      (node (ref "U13") (pin "C5") (pinfunction "PK6_C5") (pintype "passive"))
    )
    (net (code "185") (name "/PK7") (class "Default")
      (node (ref "TP15") (pin "1") (pinfunction "1_1") (pintype "passive"))
      (node (ref "U13") (pin "C4") (pinfunction "PK7_C4") (pintype "passive"))
    )
    (net (code "187") (name "/SCLK_MCLK") (class "Default")
      (node (ref "TP1") (pin "1") (pinfunction "1_1") (pintype "passive"))
    )
    (net (code "188") (name "/SWO") (class "Default")
      (node (ref "R92") (pin "1") (pinfunction "1_1") (pintype "passive"))
    )
    (net (code "189") (name "/ULPI_D0") (class "Default")
      (node (ref "U13") (pin "R2") (pinfunction "PA3_R2") (pintype "passive"))
    )
    (net (code "190") (name "/ULPI_D1") (class "Default")
      (node (ref "U13") (pin "R5") (pinfunction "PB0_R5") (pintype "passive"))
    )
    (net (code "191") (name "/ULPI_D2") (class "Default")
      (node (ref "U13") (pin "R4") (pinfunction "PB1_R4") (pintype "passive"))
    )
    (net (code "192") (name "/ULPI_D3") (class "Default")
      (node (ref "U13") (pin "P12") (pinfunction "PB10_P12") (pintype "passive"))
    )
    (net (code "193") (name "/ULPI_D4") (class "Default")
      (node (ref "U13") (pin "R13") (pinfunction "PB11_R13") (pintype "passive"))
    )
    (net (code "194") (name "/ULPI_D5") (class "Default")
      (node (ref "U13") (pin "L13") (pinfunction "PB12_L13") (pintype "passive"))
    )
    (net (code "195") (name "/ULPI_D6") (class "Default")
      (node (ref "U13") (pin "K14") (pinfunction "PB13_K14") (pintype "passive"))
    )
    (net (code "196") (name "/ULPI_D7") (class "Default")
      (node (ref "U13") (pin "A8") (pinfunction "PB5_A8") (pintype "passive"))
    )
    (net (code "198") (name "/uSD_D2") (class "Default")
      (node (ref "R93") (pin "1") (pinfunction "1_1") (pintype "passive"))
    )
    (net (code "200") (name "3V3") (class "Default")
      (node (ref "C98") (pin "2") (pinfunction "2_2") (pintype "passive"))
      (node (ref "JP4") (pin "2") (pinfunction "NO_2") (pintype "passive"))
      (node (ref "R106") (pin "2") (pinfunction "2_2") (pintype "passive"))
      (node (ref "R107") (pin "1") (pinfunction "1_1") (pintype "passive"))
      (node (ref "R109") (pin "2") (pinfunction "2_2") (pintype "passive"))
      (node (ref "R17") (pin "2") (pinfunction "2_2") (pintype "passive"))
      (node (ref "R19") (pin "1") (pinfunction "1_1") (pintype "passive"))
      (node (ref "R20") (pin "1") (pinfunction "1_1") (pintype "passive"))
      (node (ref "R89") (pin "1") (pinfunction "1_1") (pintype "passive"))
      (node (ref "R90") (pin "1") (pinfunction "1_1") (pintype "passive"))
      (node (ref "R91") (pin "1") (pinfunction "1_1") (pintype "passive"))
      (node (ref "X2") (pin "4") (pinfunction "VDD_4") (pintype "passive"))
    )
    (net (code "201") (name "DSI_VDD12") (class "Default")
      (node (ref "C23") (pin "2") (pinfunction "2_2") (pintype "passive"))
      (node (ref "C25") (pin "2") (pinfunction "2_2") (pintype "passive"))
      (node (ref "C27") (pin "2") (pinfunction "2_2") (pintype "passive"))
      (node (ref "U13") (pin "G13") (pinfunction "DSI_VDD12_0_G13") (pintype "power_in"))
      (node (ref "U13") (pin "K12") (pinfunction "DSI_VCAP_K12") (pintype "power_in"))
    )
    (net (code "202") (name "GND") (class "Default")
      (node (ref "C101") (pin "2") (pinfunction "2_2") (pintype "passive"))
      (node (ref "C102") (pin "1") (pinfunction "1_1") (pintype "passive"))
      (node (ref "C103") (pin "1") (pinfunction "1_1") (pintype "passive"))
      (node (ref "C104") (pin "1") (pinfunction "1_1") (pintype "passive"))
      (node (ref "C105") (pin "1") (pinfunction "1_1") (pintype "passive"))
      (node (ref "C106") (pin "1") (pinfunction "1_1") (pintype "passive"))
      (node (ref "C107") (pin "1") (pinfunction "1_1") (pintype "passive"))
      (node (ref "C108") (pin "1") (pinfunction "1_1") (pintype "passive"))
      (node (ref "C109") (pin "1") (pinfunction "1_1") (pintype "passive"))
      (node (ref "C110") (pin "1") (pinfunction "1_1") (pintype "passive"))
      (node (ref "C111") (pin "1") (pinfunction "1_1") (pintype "passive"))
      (node (ref "C112") (pin "1") (pinfunction "1_1") (pintype "passive"))
      (node (ref "C113") (pin "1") (pinfunction "1_1") (pintype "passive"))
      (node (ref "C114") (pin "1") (pinfunction "1_1") (pintype "passive"))
      (node (ref "C115") (pin "1") (pinfunction "1_1") (pintype "passive"))
      (node (ref "C116") (pin "2") (pinfunction "2_2") (pintype "passive"))
      (node (ref "C23") (pin "1") (pinfunction "1_1") (pintype "passive"))
      (node (ref "C25") (pin "1") (pinfunction "1_1") (pintype "passive"))
      (node (ref "C27") (pin "1") (pinfunction "1_1") (pintype "passive"))
      (node (ref "C31") (pin "1") (pinfunction "1_1") (pintype "passive"))
      (node (ref "C68") (pin "2") (pinfunction "2_2") (pintype "passive"))
      (node (ref "C69") (pin "2") (pinfunction "2_2") (pintype "passive"))
      (node (ref "C72") (pin "1") (pinfunction "1_1") (pintype "passive"))
      (node (ref "C76") (pin "1") (pinfunction "1_1") (pintype "passive"))
      (node (ref "C77") (pin "1") (pinfunction "1_1") (pintype "passive"))
      (node (ref "C80") (pin "1") (pinfunction "1_1") (pintype "passive"))
      (node (ref "C83") (pin "1") (pinfunction "1_1") (pintype "passive"))
      (node (ref "C84") (pin "1") (pinfunction "1_1") (pintype "passive"))
      (node (ref "C86") (pin "1") (pinfunction "1_1") (pintype "passive"))
      (node (ref "C88") (pin "1") (pinfunction "1_1") (pintype "passive"))
      (node (ref "C97") (pin "1") (pinfunction "1_1") (pintype "passive"))
      (node (ref "C98") (pin "1") (pinfunction "1_1") (pintype "passive"))
      (node (ref "C99") (pin "1") (pinfunction "1_1") (pintype "passive"))
      (node (ref "R108") (pin "1") (pinfunction "1_1") (pintype "passive"))
      (node (ref "R18") (pin "1") (pinfunction "1_1") (pintype "passive"))
      (node (ref "R21") (pin "1") (pinfunction "1_1") (pintype "passive"))
      (node (ref "U13") (pin "F10") (pinfunction "VSS2_F10") (pintype "passive"))
      (node (ref "U13") (pin "F2") (pinfunction "VSS13-VSS18_F2") (pintype "passive"))
      (node (ref "U13") (pin "F6") (pinfunction "VSS3_F6") (pintype "passive"))
      (node (ref "U13") (pin "F7") (pinfunction "VSS11_F7") (pintype "passive"))
      (node (ref "U13") (pin "F8") (pinfunction "VSS10_F8") (pintype "passive"))
      (node (ref "U13") (pin "F9") (pinfunction "VSS15_F9") (pintype "passive"))
      (node (ref "U13") (pin "G10") (pinfunction "VSS9_G10") (pintype "passive"))
      (node (ref "U13") (pin "G12") (pinfunction "DSI_VSS_G12") (pintype "power_in"))
      (node (ref "U13") (pin "G6") (pinfunction "VSS17_G6") (pintype "passive"))
      (node (ref "U13") (pin "H10") (pinfunction "VSS20_H10") (pintype "passive"))
      (node (ref "U13") (pin "H6") (pinfunction "VSS5_H6") (pintype "passive"))
      (node (ref "U13") (pin "J10") (pinfunction "VSS8_J10") (pintype "passive"))
      (node (ref "U13") (pin "J6") (pinfunction "VSS12_J6") (pintype "passive"))
      (node (ref "U13") (pin "K10") (pinfunction "VSS14_K10") (pintype "passive"))
      (node (ref "U13") (pin "K6") (pinfunction "VSS4_K6") (pintype "passive"))
      (node (ref "U13") (pin "K7") (pinfunction "VSS6_K7") (pintype "passive"))
      (node (ref "U13") (pin "K8") (pinfunction "VSS7_K8") (pintype "passive"))
      (node (ref "U13") (pin "K9") (pinfunction "VSS1_K9") (pintype "passive"))
      (node (ref "U13") (pin "L6") (pinfunction "VSS19_L6") (pintype "passive"))
      (node (ref "U13") (pin "M1") (pinfunction "VSSA_M1") (pintype "passive"))
      (node (ref "U13") (pin "N1") (pinfunction "VREF-_N1") (pintype "passive"))
      (node (ref "X2") (pin "2") (pinfunction "GND_2") (pintype "passive"))
    )
    (net (code "203") (name "Net-(C77-Pad2)") (class "Default")
      (node (ref "C77") (pin "2") (pinfunction "2_2") (pintype "passive"))
      (node (ref "R97") (pin "1") (pinfunction "1_1") (pintype "passive"))
      (node (ref "X1") (pin "1") (pinfunction "1_1") (pintype "passive"))
    )
    (net (code "204") (name "Net-(C84-Pad2)") (class "Default")
      (node (ref "C84") (pin "2") (pinfunction "2_2") (pintype "passive"))
      (node (ref "R99") (pin "1") (pinfunction "1_1") (pintype "passive"))
      (node (ref "X1") (pin "2") (pinfunction "2_2") (pintype "passive"))
    )
    (net (code "205") (name "Net-(U13A-PDR_ON)") (class "Default")
      (node (ref "R20") (pin "2") (pinfunction "2_2") (pintype "passive"))
      (node (ref "R21") (pin "2") (pinfunction "2_2") (pintype "passive"))
      (node (ref "U13") (pin "E5") (pinfunction "PDR_ON_E5") (pintype "passive"))
    )
    (net (code "206") (name "Net-(U13C-BYPASS-REG)") (class "Default")
      (node (ref "R108") (pin "2") (pinfunction "2_2") (pintype "passive"))
      (node (ref "U13") (pin "L5") (pinfunction "BYPASS-REG_L5") (pintype "passive"))
    )
    (net (code "207") (name "Net-(U13C-VCAP1)") (class "Default")
      (node (ref "C31") (pin "2") (pinfunction "2_2") (pintype "passive"))
      (node (ref "U13") (pin "L11") (pinfunction "VCAP1_L11") (pintype "passive"))
    )
    (net (code "208") (name "Net-(U13C-VCAP2)") (class "Default")
      (node (ref "C72") (pin "2") (pinfunction "2_2") (pintype "passive"))
      (node (ref "U13") (pin "E11") (pinfunction "VCAP2_E11") (pintype "passive"))
    )
    (net (code "209") (name "Net-(X2-EN)") (class "Default")
      (node (ref "R107") (pin "2") (pinfunction "2_2") (pintype "passive"))
      (node (ref "X2") (pin "1") (pinfunction "EN_1") (pintype "passive"))
    )
    (net (code "210") (name "VDD") (class "Default")
      (node (ref "C104") (pin "2") (pinfunction "2_2") (pintype "passive"))
      (node (ref "C105") (pin "2") (pinfunction "2_2") (pintype "passive"))
      (node (ref "C106") (pin "2") (pinfunction "2_2") (pintype "passive"))
      (node (ref "C107") (pin "2") (pinfunction "2_2") (pintype "passive"))
      (node (ref "C108") (pin "2") (pinfunction "2_2") (pintype "passive"))
      (node (ref "C109") (pin "2") (pinfunction "2_2") (pintype "passive"))
      (node (ref "C110") (pin "2") (pinfunction "2_2") (pintype "passive"))
      (node (ref "C111") (pin "2") (pinfunction "2_2") (pintype "passive"))
      (node (ref "C112") (pin "2") (pinfunction "2_2") (pintype "passive"))
      (node (ref "C113") (pin "2") (pinfunction "2_2") (pintype "passive"))
      (node (ref "C114") (pin "2") (pinfunction "2_2") (pintype "passive"))
      (node (ref "C115") (pin "2") (pinfunction "2_2") (pintype "passive"))
      (node (ref "C68") (pin "1") (pinfunction "1_1") (pintype "passive"))
      (node (ref "C69") (pin "1") (pinfunction "1_1") (pintype "passive"))
      (node (ref "C76") (pin "2") (pinfunction "2_2") (pintype "passive"))
      (node (ref "C80") (pin "2") (pinfunction "2_2") (pintype "passive"))
      (node (ref "C83") (pin "2") (pinfunction "2_2") (pintype "passive"))
      (node (ref "C86") (pin "2") (pinfunction "2_2") (pintype "passive"))
      (node (ref "C88") (pin "2") (pinfunction "2_2") (pintype "passive"))
      (node (ref "C97") (pin "2") (pinfunction "2_2") (pintype "passive"))
      (node (ref "C99") (pin "2") (pinfunction "2_2") (pintype "passive"))
      (node (ref "JP4") (pin "1") (pinfunction "COMMON_1") (pintype "passive"))
      (node (ref "L6") (pin "1") (pinfunction "1_1") (pintype "passive"))
      (node (ref "R109") (pin "1") (pinfunction "1_1") (pintype "passive"))
      (node (ref "U13") (pin "C1") (pinfunction "VBAT_C1") (pintype "passive"))
      (node (ref "U13") (pin "E10") (pinfunction "VDD15_E10") (pintype "passive"))
      (node (ref "U13") (pin "E7") (pinfunction "VDD3_E7") (pintype "passive"))
      (node (ref "U13") (pin "E8") (pinfunction "VDD11_E8") (pintype "passive"))
      (node (ref "U13") (pin "E9") (pinfunction "VDD_MMC33_E9") (pintype "passive"))
      (node (ref "U13") (pin "F11") (pinfunction "VDD2_F11") (pintype "passive"))
      (node (ref "U13") (pin "F4") (pinfunction "VDD13_F4") (pintype "passive"))
      (node (ref "U13") (pin "F5") (pinfunction "VDD17_F5") (pintype "passive"))
      (node (ref "U13") (pin "G11") (pinfunction "VDD_USB33_G11") (pintype "passive"))
      (node (ref "U13") (pin "G5") (pinfunction "VDD18_G5") (pintype "passive"))
      (node (ref "U13") (pin "H11") (pinfunction "VDD_VREGDSI_H11") (pintype "passive"))
      (node (ref "U13") (pin "H5") (pinfunction "VDD5_H5") (pintype "passive"))
      (node (ref "U13") (pin "J11") (pinfunction "VDD8_J11") (pintype "passive"))
      (node (ref "U13") (pin "J5") (pinfunction "VDD12_J5") (pintype "passive"))
      (node (ref "U13") (pin "K11") (pinfunction "VDD14_K11") (pintype "passive"))
      (node (ref "U13") (pin "K5") (pinfunction "VDD4_K5") (pintype "passive"))
      (node (ref "U13") (pin "L10") (pinfunction "VDD1_L10") (pintype "passive"))
      (node (ref "U13") (pin "L7") (pinfunction "VDD19_L7") (pintype "passive"))
      (node (ref "U13") (pin "L8") (pinfunction "VDD6_L8") (pintype "passive"))
      (node (ref "U13") (pin "L9") (pinfunction "VDD7_L9") (pintype "passive"))
    )
    (net (code "211") (name "VDDA") (class "Default")
      (node (ref "C103") (pin "2") (pinfunction "2_2") (pintype "passive"))
      (node (ref "C116") (pin "1") (pinfunction "1_1") (pintype "passive"))
      (node (ref "L6") (pin "2") (pinfunction "2_2") (pintype "passive"))
      (node (ref "R110") (pin "1") (pinfunction "1_1") (pintype "passive"))
      (node (ref "U13") (pin "R1") (pinfunction "VDDA_R1") (pintype "passive"))
    )
    (net (code "212") (name "VREF+") (class "Default")
      (node (ref "C101") (pin "1") (pinfunction "1_1") (pintype "passive"))
      (node (ref "C102") (pin "2") (pinfunction "2_2") (pintype "passive"))
      (node (ref "R110") (pin "2") (pinfunction "2_2") (pintype "passive"))
      (node (ref "U13") (pin "P1") (pinfunction "VREF+_P1") (pintype "passive"))
    )
  )
)
